# esp8266-board.net
KiCad netlist of a schematic drawn in EAGLE
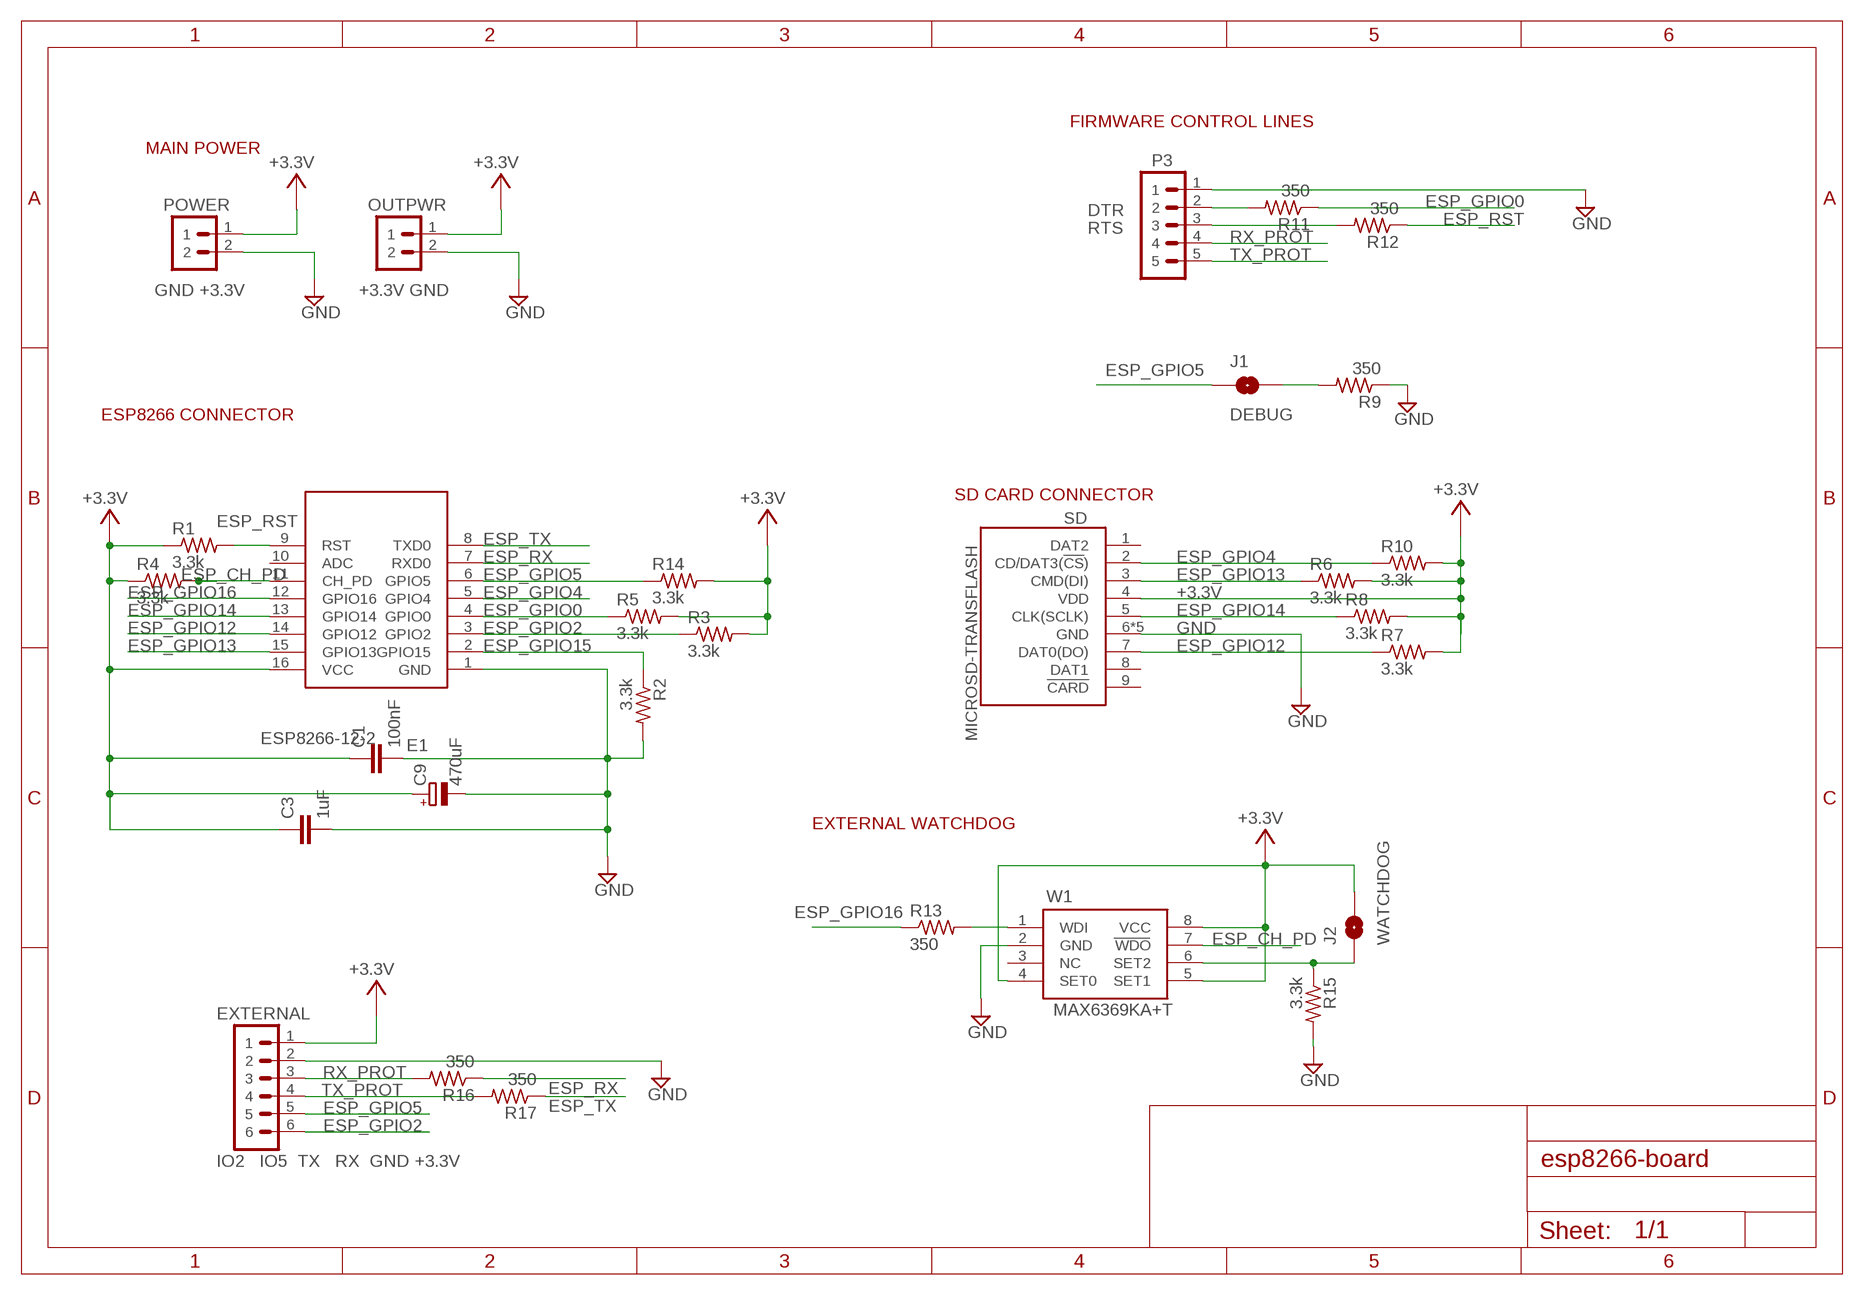
[diagram p0: schematic, sheet 1]

(export (version "E")
  (design (tool "Eeschema 10.0.6"))
  (components
    (comp (ref "C1")
      (value "100nF")
      (footprint "eagle-import:SMD0805")
      (libsource (lib "eagle-import") (part "CAPACITOR0805"))
    )
    (comp (ref "C3")
      (value "1uF")
      (footprint "eagle-import:SMD0805")
      (libsource (lib "eagle-import") (part "CAPACITOR0805"))
    )
    (comp (ref "C9")
      (value "470uF")
      (footprint "eagle-import:E2,5-6")
      (libsource (lib "eagle-import") (part "CPOL-EUE2.5-6"))
    )
    (comp (ref "E1")
      (value "ESP8266-12-2")
      (footprint "eagle-import:ESP8266-12-2")
      (libsource (lib "eagle-import") (part "ESP8266-12-2"))
    )
    (comp (ref "EXTERNAL")
      (value "IO2 IO5 TX RX GND +3.3V")
      (footprint "eagle-import:PIN-HEADER-6PIN")
      (libsource (lib "eagle-import") (part "PIN-HEADER-6PIN"))
    )
    (comp (ref "J1")
      (value "DEBUG")
      (footprint "eagle-import:JUMPER-PAD-2-ROUND")
      (libsource (lib "eagle-import") (part "JUMPER-PAD-2ROUND"))
    )
    (comp (ref "J2")
      (value "WATCHDOG")
      (footprint "eagle-import:JUMPER-PAD-2-ROUND")
      (libsource (lib "eagle-import") (part "JUMPER-PAD-2ROUND"))
    )
    (comp (ref "OUTPWR")
      (value "+3.3V GND")
      (footprint "eagle-import:PIN-HEADER-2PIN")
      (libsource (lib "eagle-import") (part "PIN-HEADER-2PIN"))
    )
    (comp (ref "P3")
      (value "GND DTR RTS RX TX")
      (footprint "eagle-import:PIN-HEADER-5PIN")
      (libsource (lib "eagle-import") (part "PIN-HEADER-5PIN"))
    )
    (comp (ref "POWER")
      (value "GND +3.3V")
      (footprint "eagle-import:PIN-HEADER-2PIN")
      (libsource (lib "eagle-import") (part "PIN-HEADER-2PIN"))
    )
    (comp (ref "R1")
      (value "3.3k")
      (footprint "eagle-import:SMD0805")
      (libsource (lib "eagle-import") (part "RESISTOR0805"))
    )
    (comp (ref "R2")
      (value "3.3k")
      (footprint "eagle-import:SMD0805")
      (libsource (lib "eagle-import") (part "RESISTOR0805"))
    )
    (comp (ref "R3")
      (value "3.3k")
      (footprint "eagle-import:SMD0805")
      (libsource (lib "eagle-import") (part "RESISTOR0805"))
    )
    (comp (ref "R4")
      (value "3.3k")
      (footprint "eagle-import:SMD0805")
      (libsource (lib "eagle-import") (part "RESISTOR0805"))
    )
    (comp (ref "R5")
      (value "3.3k")
      (footprint "eagle-import:SMD0805")
      (libsource (lib "eagle-import") (part "RESISTOR0805"))
    )
    (comp (ref "R6")
      (value "3.3k")
      (footprint "eagle-import:SMD0805")
      (libsource (lib "eagle-import") (part "RESISTOR0805"))
    )
    (comp (ref "R7")
      (value "3.3k")
      (footprint "eagle-import:SMD0805")
      (libsource (lib "eagle-import") (part "RESISTOR0805"))
    )
    (comp (ref "R8")
      (value "3.3k")
      (footprint "eagle-import:SMD0805")
      (libsource (lib "eagle-import") (part "RESISTOR0805"))
    )
    (comp (ref "R9")
      (value "350")
      (footprint "eagle-import:SMD0805")
      (libsource (lib "eagle-import") (part "RESISTOR0805"))
    )
    (comp (ref "R10")
      (value "3.3k")
      (footprint "eagle-import:SMD0805")
      (libsource (lib "eagle-import") (part "RESISTOR0805"))
    )
    (comp (ref "R11")
      (value "350")
      (footprint "eagle-import:SMD0805")
      (libsource (lib "eagle-import") (part "RESISTOR0805"))
    )
    (comp (ref "R12")
      (value "350")
      (footprint "eagle-import:SMD0805")
      (libsource (lib "eagle-import") (part "RESISTOR0805"))
    )
    (comp (ref "R13")
      (value "350")
      (footprint "eagle-import:SMD0805")
      (libsource (lib "eagle-import") (part "RESISTOR0805"))
    )
    (comp (ref "R14")
      (value "3.3k")
      (footprint "eagle-import:SMD0805")
      (libsource (lib "eagle-import") (part "RESISTOR0805"))
    )
    (comp (ref "R15")
      (value "3.3k")
      (footprint "eagle-import:SMD0805")
      (libsource (lib "eagle-import") (part "RESISTOR0805"))
    )
    (comp (ref "R16")
      (value "350")
      (footprint "eagle-import:SMD0805")
      (libsource (lib "eagle-import") (part "RESISTOR0805"))
    )
    (comp (ref "R17")
      (value "350")
      (footprint "eagle-import:SMD0805")
      (libsource (lib "eagle-import") (part "RESISTOR0805"))
    )
    (comp (ref "SD")
      (value "MICROSD-TRANSFLASH")
      (footprint "eagle-import:MICROSD-TRANSFLASH")
      (libsource (lib "eagle-import") (part "MICROSD-TRANSFLASH"))
    )
    (comp (ref "W1")
      (value "MAX6369KA+T")
      (footprint "eagle-import:SOT23-8")
      (libsource (lib "eagle-import") (part "MAX6369-74"))
    )
  )
  (nets
    (net (code "1") (name "+3.3V") (class "Default")
      (node (ref "C1") (pin "1") (pinfunction "1_1") (pintype "passive"))
      (node (ref "C3") (pin "1") (pinfunction "1_1") (pintype "passive"))
      (node (ref "C9") (pin "+") (pinfunction "+_+") (pintype "passive"))
      (node (ref "E1") (pin "16") (pinfunction "VCC_16") (pintype "power_in"))
      (node (ref "EXTERNAL") (pin "1") (pinfunction "1_1") (pintype "passive"))
      (node (ref "J2") (pin "2") (pinfunction "2_2") (pintype "passive"))
      (node (ref "OUTPWR") (pin "1") (pinfunction "1_1") (pintype "passive"))
      (node (ref "POWER") (pin "1") (pinfunction "1_1") (pintype "passive"))
      (node (ref "R1") (pin "1") (pinfunction "1_1") (pintype "passive"))
      (node (ref "R10") (pin "2") (pinfunction "2_2") (pintype "passive"))
      (node (ref "R14") (pin "2") (pinfunction "2_2") (pintype "passive"))
      (node (ref "R3") (pin "2") (pinfunction "2_2") (pintype "passive"))
      (node (ref "R4") (pin "1") (pinfunction "1_1") (pintype "passive"))
      (node (ref "R5") (pin "2") (pinfunction "2_2") (pintype "passive"))
      (node (ref "R6") (pin "2") (pinfunction "2_2") (pintype "passive"))
      (node (ref "R7") (pin "2") (pinfunction "2_2") (pintype "passive"))
      (node (ref "R8") (pin "2") (pinfunction "2_2") (pintype "passive"))
      (node (ref "SD") (pin "4") (pinfunction "VDD_4") (pintype "power_in"))
      (node (ref "W1") (pin "4") (pinfunction "SET0_4") (pintype "input"))
      (node (ref "W1") (pin "5") (pinfunction "SET1_5") (pintype "input"))
      (node (ref "W1") (pin "8") (pinfunction "VCC_8") (pintype "power_in"))
    )
    (net (code "2") (name "/ESP_CH_PD") (class "Default")
      (node (ref "E1") (pin "11") (pinfunction "CH_PD_11") (pintype "input"))
      (node (ref "R4") (pin "2") (pinfunction "2_2") (pintype "passive"))
      (node (ref "W1") (pin "7") (pinfunction "WDO_7") (pintype "output"))
    )
    (net (code "3") (name "/ESP_GPIO0") (class "Default")
      (node (ref "E1") (pin "4") (pinfunction "GPIO0_4") (pintype "bidirectional"))
      (node (ref "R11") (pin "1") (pinfunction "1_1") (pintype "passive"))
      (node (ref "R5") (pin "1") (pinfunction "1_1") (pintype "passive"))
    )
    (net (code "4") (name "/ESP_GPIO2") (class "Default")
      (node (ref "E1") (pin "3") (pinfunction "GPIO2_3") (pintype "bidirectional"))
      (node (ref "EXTERNAL") (pin "6") (pinfunction "6_6") (pintype "passive"))
      (node (ref "R3") (pin "1") (pinfunction "1_1") (pintype "passive"))
    )
    (net (code "5") (name "/ESP_GPIO4") (class "Default")
      (node (ref "E1") (pin "5") (pinfunction "GPIO4_5") (pintype "bidirectional"))
      (node (ref "R10") (pin "1") (pinfunction "1_1") (pintype "passive"))
      (node (ref "SD") (pin "2") (pinfunction "CD/DAT3(~{CS})_2") (pintype "bidirectional"))
    )
    (net (code "6") (name "/ESP_GPIO5") (class "Default")
      (node (ref "E1") (pin "6") (pinfunction "GPIO5_6") (pintype "bidirectional"))
      (node (ref "EXTERNAL") (pin "5") (pinfunction "5_5") (pintype "passive"))
      (node (ref "J1") (pin "1") (pinfunction "1_1") (pintype "passive"))
      (node (ref "R14") (pin "1") (pinfunction "1_1") (pintype "passive"))
    )
    (net (code "7") (name "/ESP_GPIO12") (class "Default")
      (node (ref "E1") (pin "14") (pinfunction "GPIO12_14") (pintype "bidirectional"))
      (node (ref "R7") (pin "1") (pinfunction "1_1") (pintype "passive"))
      (node (ref "SD") (pin "7") (pinfunction "DAT0(DO)_7") (pintype "bidirectional"))
    )
    (net (code "8") (name "/ESP_GPIO13") (class "Default")
      (node (ref "E1") (pin "15") (pinfunction "GPIO13_15") (pintype "bidirectional"))
      (node (ref "R6") (pin "1") (pinfunction "1_1") (pintype "passive"))
      (node (ref "SD") (pin "3") (pinfunction "CMD(DI)_3") (pintype "bidirectional"))
    )
    (net (code "9") (name "/ESP_GPIO14") (class "Default")
      (node (ref "E1") (pin "13") (pinfunction "GPIO14_13") (pintype "bidirectional"))
      (node (ref "R8") (pin "1") (pinfunction "1_1") (pintype "passive"))
      (node (ref "SD") (pin "5") (pinfunction "CLK(SCLK)_5") (pintype "input"))
    )
    (net (code "10") (name "/ESP_GPIO15") (class "Default")
      (node (ref "E1") (pin "2") (pinfunction "GPIO15_2") (pintype "bidirectional"))
      (node (ref "R2") (pin "1") (pinfunction "1_1") (pintype "passive"))
    )
    (net (code "11") (name "/ESP_GPIO16") (class "Default")
      (node (ref "E1") (pin "12") (pinfunction "GPIO16_12") (pintype "bidirectional"))
      (node (ref "R13") (pin "1") (pinfunction "1_1") (pintype "passive"))
    )
    (net (code "12") (name "/ESP_RST") (class "Default")
      (node (ref "E1") (pin "9") (pinfunction "RST_9") (pintype "input"))
      (node (ref "R1") (pin "2") (pinfunction "2_2") (pintype "passive"))
      (node (ref "R12") (pin "1") (pinfunction "1_1") (pintype "passive"))
    )
    (net (code "13") (name "/ESP_RX") (class "Default")
      (node (ref "E1") (pin "7") (pinfunction "RXD0_7") (pintype "input"))
      (node (ref "R16") (pin "1") (pinfunction "1_1") (pintype "passive"))
    )
    (net (code "14") (name "/ESP_TX") (class "Default")
      (node (ref "E1") (pin "8") (pinfunction "TXD0_8") (pintype "output"))
      (node (ref "R17") (pin "1") (pinfunction "1_1") (pintype "passive"))
    )
    (net (code "15") (name "/RX_PROT") (class "Default")
      (node (ref "EXTERNAL") (pin "3") (pinfunction "3_3") (pintype "passive"))
      (node (ref "P3") (pin "4") (pinfunction "4_4") (pintype "passive"))
      (node (ref "R16") (pin "2") (pinfunction "2_2") (pintype "passive"))
    )
    (net (code "16") (name "/TX_PROT") (class "Default")
      (node (ref "EXTERNAL") (pin "4") (pinfunction "4_4") (pintype "passive"))
      (node (ref "P3") (pin "5") (pinfunction "5_5") (pintype "passive"))
      (node (ref "R17") (pin "2") (pinfunction "2_2") (pintype "passive"))
    )
    (net (code "17") (name "GND") (class "Default")
      (node (ref "C1") (pin "2") (pinfunction "2_2") (pintype "passive"))
      (node (ref "C3") (pin "2") (pinfunction "2_2") (pintype "passive"))
      (node (ref "C9") (pin "-") (pinfunction "-_-") (pintype "passive"))
      (node (ref "E1") (pin "1") (pinfunction "GND_1") (pintype "power_in"))
      (node (ref "EXTERNAL") (pin "2") (pinfunction "2_2") (pintype "passive"))
      (node (ref "OUTPWR") (pin "2") (pinfunction "2_2") (pintype "passive"))
      (node (ref "P3") (pin "1") (pinfunction "1_1") (pintype "passive"))
      (node (ref "POWER") (pin "2") (pinfunction "2_2") (pintype "passive"))
      (node (ref "R15") (pin "2") (pinfunction "2_2") (pintype "passive"))
      (node (ref "R2") (pin "2") (pinfunction "2_2") (pintype "passive"))
      (node (ref "R9") (pin "1") (pinfunction "1_1") (pintype "passive"))
      (node (ref "SD") (pin "6") (pinfunction "GND_6") (pintype "power_in"))
      (node (ref "SD") (pin "S1") (pinfunction "GND_S1") (pintype "power_in"))
      (node (ref "SD") (pin "S2") (pinfunction "GND_S2") (pintype "power_in"))
      (node (ref "SD") (pin "S3") (pinfunction "GND_S3") (pintype "power_in"))
      (node (ref "SD") (pin "S4") (pinfunction "GND_S4") (pintype "power_in"))
      (node (ref "W1") (pin "2") (pinfunction "GND_2") (pintype "power_in"))
    )
    (net (code "18") (name "Net-(J1-Pad2)") (class "Default")
      (node (ref "J1") (pin "2") (pinfunction "2_2") (pintype "passive"))
      (node (ref "R9") (pin "2") (pinfunction "2_2") (pintype "passive"))
    )
    (net (code "19") (name "Net-(P3-Pad2)") (class "Default")
      (node (ref "P3") (pin "2") (pinfunction "2_2") (pintype "passive"))
      (node (ref "R11") (pin "2") (pinfunction "2_2") (pintype "passive"))
    )
    (net (code "20") (name "Net-(P3-Pad3)") (class "Default")
      (node (ref "P3") (pin "3") (pinfunction "3_3") (pintype "passive"))
      (node (ref "R12") (pin "2") (pinfunction "2_2") (pintype "passive"))
    )
    (net (code "21") (name "Net-(W1-SET2)") (class "Default")
      (node (ref "J2") (pin "1") (pinfunction "1_1") (pintype "passive"))
      (node (ref "R15") (pin "1") (pinfunction "1_1") (pintype "passive"))
      (node (ref "W1") (pin "6") (pinfunction "SET2_6") (pintype "input"))
    )
    (net (code "22") (name "Net-(W1-WDI)") (class "Default")
      (node (ref "R13") (pin "2") (pinfunction "2_2") (pintype "passive"))
      (node (ref "W1") (pin "1") (pinfunction "WDI_1") (pintype "input"))
    )
    (net (code "23") (name "unconnected-(E1-ADC-Pad10)") (class "Default")
      (node (ref "E1") (pin "10") (pinfunction "ADC_10") (pintype "input"))
    )
    (net (code "24") (name "unconnected-(SD-DAT1-Pad8)") (class "Default")
      (node (ref "SD") (pin "8") (pinfunction "DAT1_8") (pintype "bidirectional"))
    )
    (net (code "25") (name "unconnected-(SD-DAT2-Pad1)") (class "Default")
      (node (ref "SD") (pin "1") (pinfunction "DAT2_1") (pintype "bidirectional"))
    )
    (net (code "26") (name "unconnected-(SD-~{CARD}-Pad9)") (class "Default")
      (node (ref "SD") (pin "9") (pinfunction "~{CARD}_9") (pintype "passive"))
    )
    (net (code "27") (name "unconnected-(W1-NC-Pad3)") (class "Default")
      (node (ref "W1") (pin "3") (pinfunction "NC_3") (pintype "no_connect"))
    )
  )
)
